# ECE411-Group6-V3.net
KiCad netlist of a schematic drawn in EAGLE
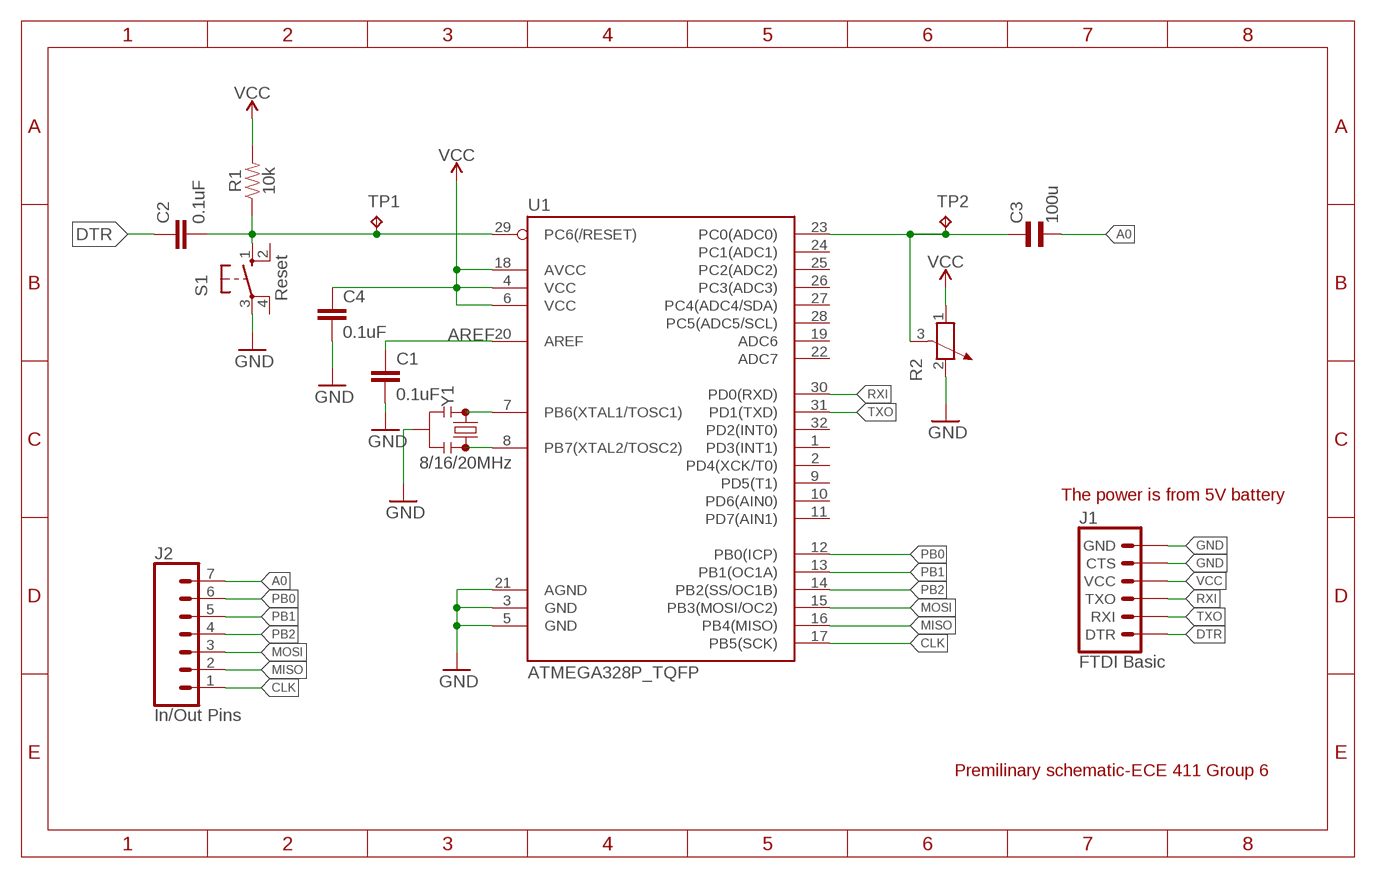
[diagram p0: schematic, sheet 1]

(export (version "E")
  (design (tool "Eeschema 10.0.6"))
  (components
    (comp (ref "C1")
      (value "0.1uF")
      (footprint "eagle-import:0603")
      (libsource (lib "eagle-import") (part "0.1UF-0603-25V-5%"))
    )
    (comp (ref "C2")
      (value "0.1uF")
      (footprint "eagle-import:0603")
      (libsource (lib "eagle-import") (part "0.1UF-0603-25V-5%"))
    )
    (comp (ref "C3")
      (value "100u")
      (footprint "eagle-import:EU25-10")
      (libsource (lib "eagle-import") (part "EL-BI25-10AXIAL"))
    )
    (comp (ref "C4")
      (value "0.1uF")
      (footprint "eagle-import:0603")
      (libsource (lib "eagle-import") (part "0.1UF-0603-25V-5%"))
    )
    (comp (ref "J1")
      (value "FTDI Basic")
      (footprint "eagle-import:1X06")
      (libsource (lib "eagle-import") (part "6_PIN_SERIAL_TARGET"))
    )
    (comp (ref "J2")
      (value "In/Out Pins")
      (footprint "eagle-import:1X07")
      (libsource (lib "eagle-import") (part "CONN_07"))
    )
    (comp (ref "R1")
      (value "10k")
      (footprint "eagle-import:0603")
      (libsource (lib "eagle-import") (part "10KOHM-0603-1/10W-1%"))
    )
    (comp (ref "R2")
      (value "POTENTIOMETER_PT-10")
      (footprint "eagle-import:PT-10")
      (libsource (lib "eagle-import") (part "POTENTIOMETER_PT-10"))
    )
    (comp (ref "S1")
      (value "Reset")
      (footprint "eagle-import:B3F-10XX")
      (fields (field (name "MPN") "B3F-1000"))
      (libsource (lib "eagle-import") (part "10-XX"))
    )
    (comp (ref "TP1")
      (value "TPB1,27")
      (footprint "eagle-import:B1,27")
      (libsource (lib "eagle-import") (part "TPB1,27"))
    )
    (comp (ref "TP2")
      (value "TPB1,27")
      (footprint "eagle-import:B1,27")
      (libsource (lib "eagle-import") (part "TPB1,27"))
    )
    (comp (ref "U1")
      (value "ATMEGA328P_TQFP")
      (footprint "eagle-import:TQFP32-08")
      (libsource (lib "eagle-import") (part "ATMEGA328P_TQFP"))
    )
    (comp (ref "Y1")
      (value "8/16/20MHz")
      (footprint "eagle-import:RESONATOR-SMD-3.2X1.3")
      (libsource (lib "eagle-import") (part "RESONATORSMD-3.2X1.3"))
    )
  )
  (nets
    (net (code "1") (name "/AREF") (class "Default")
      (node (ref "C1") (pin "1") (pinfunction "1_1") (pintype "passive"))
      (node (ref "U1") (pin "20") (pinfunction "AREF_20") (pintype "bidirectional"))
    )
    (net (code "2") (name "A0") (class "Default")
      (node (ref "C3") (pin "2") (pinfunction "2_2") (pintype "passive"))
      (node (ref "J2") (pin "7") (pinfunction "7_7") (pintype "passive"))
    )
    (net (code "3") (name "CLK") (class "Default")
      (node (ref "J2") (pin "1") (pinfunction "1_1") (pintype "passive"))
      (node (ref "U1") (pin "17") (pinfunction "PB5(SCK)_17") (pintype "bidirectional"))
    )
    (net (code "4") (name "DTR") (class "Default")
      (node (ref "C2") (pin "1") (pinfunction "1_1") (pintype "passive"))
      (node (ref "J1") (pin "1") (pinfunction "DTR_1") (pintype "passive"))
    )
    (net (code "5") (name "GND") (class "Default")
      (node (ref "C1") (pin "2") (pinfunction "2_2") (pintype "passive"))
      (node (ref "C4") (pin "2") (pinfunction "2_2") (pintype "passive"))
      (node (ref "J1") (pin "5") (pinfunction "CTS_5") (pintype "passive"))
      (node (ref "J1") (pin "6") (pinfunction "GND_6") (pintype "passive"))
      (node (ref "R2") (pin "2") (pinfunction "2_2") (pintype "passive"))
      (node (ref "S1") (pin "3") (pinfunction "P_3") (pintype "passive"))
      (node (ref "U1") (pin "21") (pinfunction "AGND_21") (pintype "bidirectional"))
      (node (ref "U1") (pin "3") (pinfunction "GND_3") (pintype "bidirectional"))
      (node (ref "U1") (pin "5") (pinfunction "GND_5") (pintype "bidirectional"))
      (node (ref "Y1") (pin "2") (pinfunction "2_2") (pintype "passive"))
    )
    (net (code "6") (name "MISO") (class "Default")
      (node (ref "J2") (pin "2") (pinfunction "2_2") (pintype "passive"))
      (node (ref "U1") (pin "16") (pinfunction "PB4(MISO)_16") (pintype "bidirectional"))
    )
    (net (code "7") (name "MOSI") (class "Default")
      (node (ref "J2") (pin "3") (pinfunction "3_3") (pintype "passive"))
      (node (ref "U1") (pin "15") (pinfunction "PB3(MOSI/OC2)_15") (pintype "bidirectional"))
    )
    (net (code "8") (name "Net-(S1-S)") (class "Default")
      (node (ref "C2") (pin "2") (pinfunction "2_2") (pintype "passive"))
      (node (ref "R1") (pin "1") (pinfunction "1_1") (pintype "passive"))
      (node (ref "S1") (pin "1") (pinfunction "S_1") (pintype "passive"))
      (node (ref "TP1") (pin "TP") (pinfunction "TP_TP") (pintype "input"))
      (node (ref "U1") (pin "29") (pinfunction "PC6(/RESET)_29") (pintype "bidirectional"))
    )
    (net (code "9") (name "Net-(U1-PB6(XTAL1{slash}TOSC1))") (class "Default")
      (node (ref "U1") (pin "7") (pinfunction "PB6(XTAL1/TOSC1)_7") (pintype "bidirectional"))
      (node (ref "Y1") (pin "1") (pinfunction "1_1") (pintype "passive"))
    )
    (net (code "10") (name "Net-(U1-PB7(XTAL2{slash}TOSC2))") (class "Default")
      (node (ref "U1") (pin "8") (pinfunction "PB7(XTAL2/TOSC2)_8") (pintype "bidirectional"))
      (node (ref "Y1") (pin "3") (pinfunction "3_3") (pintype "passive"))
    )
    (net (code "11") (name "Net-(U1-PC0(ADC0))") (class "Default")
      (node (ref "C3") (pin "1") (pinfunction "1_1") (pintype "passive"))
      (node (ref "R2") (pin "3") (pinfunction "3_3") (pintype "passive"))
      (node (ref "TP2") (pin "TP") (pinfunction "TP_TP") (pintype "input"))
      (node (ref "U1") (pin "23") (pinfunction "PC0(ADC0)_23") (pintype "bidirectional"))
    )
    (net (code "12") (name "PB0") (class "Default")
      (node (ref "J2") (pin "6") (pinfunction "6_6") (pintype "passive"))
      (node (ref "U1") (pin "12") (pinfunction "PB0(ICP)_12") (pintype "bidirectional"))
    )
    (net (code "13") (name "PB1") (class "Default")
      (node (ref "J2") (pin "5") (pinfunction "5_5") (pintype "passive"))
      (node (ref "U1") (pin "13") (pinfunction "PB1(OC1A)_13") (pintype "bidirectional"))
    )
    (net (code "14") (name "PB2") (class "Default")
      (node (ref "J2") (pin "4") (pinfunction "4_4") (pintype "passive"))
      (node (ref "U1") (pin "14") (pinfunction "PB2(SS/OC1B)_14") (pintype "bidirectional"))
    )
    (net (code "15") (name "RXI") (class "Default")
      (node (ref "J1") (pin "3") (pinfunction "TXO_3") (pintype "passive"))
      (node (ref "U1") (pin "30") (pinfunction "PD0(RXD)_30") (pintype "bidirectional"))
    )
    (net (code "16") (name "TXO") (class "Default")
      (node (ref "J1") (pin "2") (pinfunction "RXI_2") (pintype "passive"))
      (node (ref "U1") (pin "31") (pinfunction "PD1(TXD)_31") (pintype "bidirectional"))
    )
    (net (code "17") (name "VCC") (class "Default")
      (node (ref "C4") (pin "1") (pinfunction "1_1") (pintype "passive"))
      (node (ref "J1") (pin "4") (pinfunction "VCC_4") (pintype "passive"))
      (node (ref "R1") (pin "2") (pinfunction "2_2") (pintype "passive"))
      (node (ref "R2") (pin "1") (pinfunction "1_1") (pintype "passive"))
      (node (ref "U1") (pin "18") (pinfunction "AVCC_18") (pintype "bidirectional"))
      (node (ref "U1") (pin "4") (pinfunction "VCC_4") (pintype "bidirectional"))
      (node (ref "U1") (pin "6") (pinfunction "VCC_6") (pintype "bidirectional"))
    )
    (net (code "18") (name "unconnected-(S1-P1-Pad4)") (class "Default")
      (node (ref "S1") (pin "4") (pinfunction "P1_4") (pintype "passive"))
    )
    (net (code "19") (name "unconnected-(S1-S1-Pad2)") (class "Default")
      (node (ref "S1") (pin "2") (pinfunction "S1_2") (pintype "passive"))
    )
    (net (code "20") (name "unconnected-(U1-ADC6-Pad19)") (class "Default")
      (node (ref "U1") (pin "19") (pinfunction "ADC6_19") (pintype "bidirectional"))
    )
    (net (code "21") (name "unconnected-(U1-ADC7-Pad22)") (class "Default")
      (node (ref "U1") (pin "22") (pinfunction "ADC7_22") (pintype "bidirectional"))
    )
    (net (code "22") (name "unconnected-(U1-PC1(ADC1)-Pad24)") (class "Default")
      (node (ref "U1") (pin "24") (pinfunction "PC1(ADC1)_24") (pintype "bidirectional"))
    )
    (net (code "23") (name "unconnected-(U1-PC2(ADC2)-Pad25)") (class "Default")
      (node (ref "U1") (pin "25") (pinfunction "PC2(ADC2)_25") (pintype "bidirectional"))
    )
    (net (code "24") (name "unconnected-(U1-PC3(ADC3)-Pad26)") (class "Default")
      (node (ref "U1") (pin "26") (pinfunction "PC3(ADC3)_26") (pintype "bidirectional"))
    )
    (net (code "25") (name "unconnected-(U1-PC4(ADC4{slash}SDA)-Pad27)") (class "Default")
      (node (ref "U1") (pin "27") (pinfunction "PC4(ADC4/SDA)_27") (pintype "bidirectional"))
    )
    (net (code "26") (name "unconnected-(U1-PC5(ADC5{slash}SCL)-Pad28)") (class "Default")
      (node (ref "U1") (pin "28") (pinfunction "PC5(ADC5/SCL)_28") (pintype "bidirectional"))
    )
    (net (code "27") (name "unconnected-(U1-PD2(INT0)-Pad32)") (class "Default")
      (node (ref "U1") (pin "32") (pinfunction "PD2(INT0)_32") (pintype "bidirectional"))
    )
    (net (code "28") (name "unconnected-(U1-PD3(INT1)-Pad1)") (class "Default")
      (node (ref "U1") (pin "1") (pinfunction "PD3(INT1)_1") (pintype "bidirectional"))
    )
    (net (code "29") (name "unconnected-(U1-PD4(XCK{slash}T0)-Pad2)") (class "Default")
      (node (ref "U1") (pin "2") (pinfunction "PD4(XCK/T0)_2") (pintype "bidirectional"))
    )
    (net (code "30") (name "unconnected-(U1-PD5(T1)-Pad9)") (class "Default")
      (node (ref "U1") (pin "9") (pinfunction "PD5(T1)_9") (pintype "bidirectional"))
    )
    (net (code "31") (name "unconnected-(U1-PD6(AIN0)-Pad10)") (class "Default")
      (node (ref "U1") (pin "10") (pinfunction "PD6(AIN0)_10") (pintype "bidirectional"))
    )
    (net (code "32") (name "unconnected-(U1-PD7(AIN1)-Pad11)") (class "Default")
      (node (ref "U1") (pin "11") (pinfunction "PD7(AIN1)_11") (pintype "bidirectional"))
    )
  )
)
